# Power_Supply.net
KiCad netlist of a schematic drawn in Altium Designer
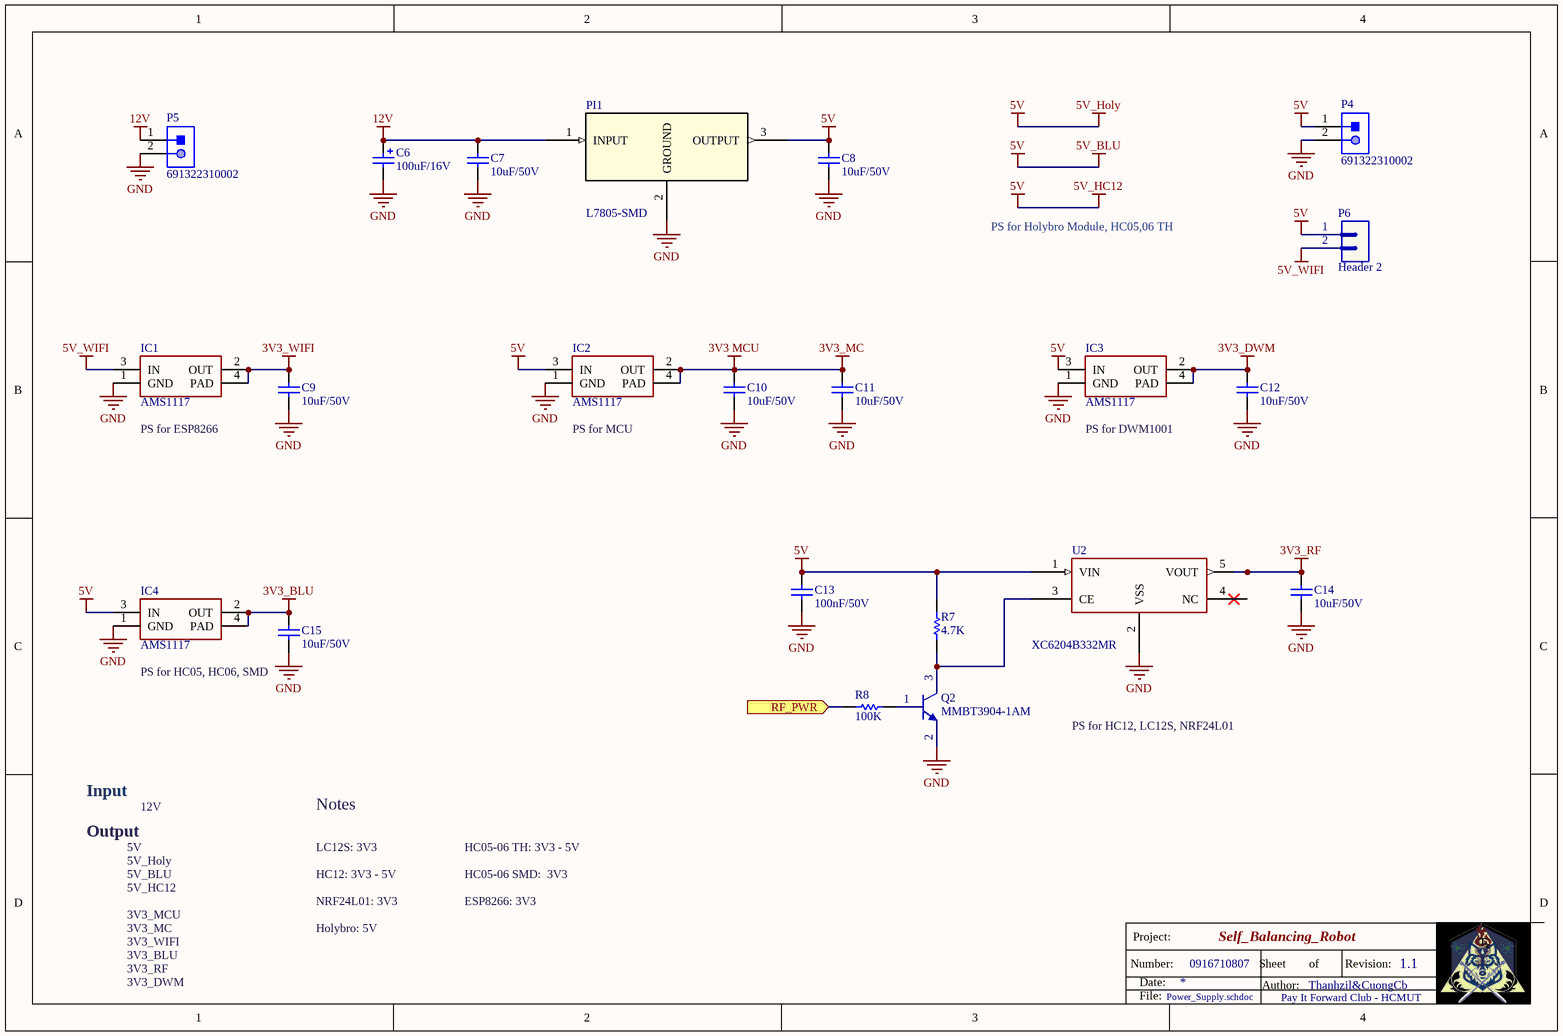
[diagram p0: Power_Supply.SchDoc]

(export (version "E")
  (design (tool "Eeschema 10.0.6"))
  (components
    (comp (ref "C6")
      (value "100uF/16V")
      (footprint "CAP-SM-AL-SIZE-D-D6L6")
      (description "CAP ALUM 100UF 20% 16V SMD")
      (fields
        (field (name "MANUFACTURER") "Nichicon")
        (field (name "MANUFACTURER PART NUMBER") "UWX1C101MCL1GB")
      )
      (libsource (lib "Capacitor") (part "Cap-Al-100uF-16V-D6L5"))
    )
    (comp (ref "C7")
      (value "10uF/50V")
      (footprint "CAP-SM-0805")
      (description "CAP CER 10UF 50V X5R 0805")
      (fields
        (field (name "MANUFACTURER") "Yageo")
        (field (name "MANUFACTURER PART NUMBER") "CC0805KKX5R9BB106")
      )
      (libsource (lib "Capacitor") (part "Cap-10uF-50V-0805"))
    )
    (comp (ref "C8")
      (value "10uF/50V")
      (footprint "CAP-SM-0805")
      (description "CAP CER 10UF 50V X5R 0805")
      (fields
        (field (name "MANUFACTURER") "Yageo")
        (field (name "MANUFACTURER PART NUMBER") "CC0805KKX5R9BB106")
      )
      (libsource (lib "Capacitor") (part "Cap-10uF-50V-0805"))
    )
    (comp (ref "C9")
      (value "10uF/50V")
      (footprint "CAP-SM-0805")
      (description "CAP CER 10UF 50V X5R 0805")
      (fields
        (field (name "MANUFACTURER") "Yageo")
        (field (name "MANUFACTURER PART NUMBER") "CC0805KKX5R9BB106")
      )
      (libsource (lib "Capacitor") (part "Cap-10uF-50V-0805"))
    )
    (comp (ref "C10")
      (value "10uF/50V")
      (footprint "CAP-SM-0805")
      (description "CAP CER 10UF 50V X5R 0805")
      (fields
        (field (name "MANUFACTURER") "Yageo")
        (field (name "MANUFACTURER PART NUMBER") "CC0805KKX5R9BB106")
      )
      (libsource (lib "Capacitor") (part "Cap-10uF-50V-0805"))
    )
    (comp (ref "C11")
      (value "10uF/50V")
      (footprint "CAP-SM-0805")
      (description "CAP CER 10UF 50V X5R 0805")
      (fields
        (field (name "MANUFACTURER") "Yageo")
        (field (name "MANUFACTURER PART NUMBER") "CC0805KKX5R9BB106")
      )
      (libsource (lib "Capacitor") (part "Cap-10uF-50V-0805"))
    )
    (comp (ref "C12")
      (value "10uF/50V")
      (footprint "CAP-SM-0805")
      (description "CAP CER 10UF 50V X5R 0805")
      (fields
        (field (name "MANUFACTURER") "Yageo")
        (field (name "MANUFACTURER PART NUMBER") "CC0805KKX5R9BB106")
      )
      (libsource (lib "Capacitor") (part "Cap-10uF-50V-0805"))
    )
    (comp (ref "C13")
      (value "100nF/50V")
      (footprint "CAP-SM-0805")
      (description "CAP CER 0.1UF 50V Y5V 0805")
      (fields
        (field (name "MANUFACTURER") "Samsung Electro-Mechanics")
        (field (name "MANUFACTURER PART NUMBER") "CL21F104ZBCNNNC")
      )
      (libsource (lib "Capacitor") (part "Cap-100nF-50V-0805"))
    )
    (comp (ref "C14")
      (value "10uF/50V")
      (footprint "CAP-SM-0805")
      (description "CAP CER 10UF 50V X5R 0805")
      (fields
        (field (name "MANUFACTURER") "Yageo")
        (field (name "MANUFACTURER PART NUMBER") "CC0805KKX5R9BB106")
      )
      (libsource (lib "Capacitor") (part "Cap-10uF-50V-0805"))
    )
    (comp (ref "C15")
      (value "10uF/50V")
      (footprint "CAP-SM-0805")
      (description "CAP CER 10UF 50V X5R 0805")
      (fields
        (field (name "MANUFACTURER") "Yageo")
        (field (name "MANUFACTURER PART NUMBER") "CC0805KKX5R9BB106")
      )
      (libsource (lib "Capacitor") (part "Cap-10uF-50V-0805"))
    )
    (comp (ref "IC1")
      (value "AMS1117")
      (footprint "SOT223")
      (description "Available in 1.8V, 2.5V, 2.85V, 3.3V, 5V, and  Adjustable Versions")
      (libsource (lib "PI") (part "AMS1117"))
    )
    (comp (ref "IC2")
      (value "AMS1117")
      (footprint "SOT223")
      (description "Available in 1.8V, 2.5V, 2.85V, 3.3V, 5V, and  Adjustable Versions")
      (libsource (lib "PI") (part "AMS1117"))
    )
    (comp (ref "IC3")
      (value "AMS1117")
      (footprint "SOT223")
      (description "Available in 1.8V, 2.5V, 2.85V, 3.3V, 5V, and  Adjustable Versions")
      (libsource (lib "PI") (part "AMS1117"))
    )
    (comp (ref "IC4")
      (value "AMS1117")
      (footprint "SOT223")
      (description "Available in 1.8V, 2.5V, 2.85V, 3.3V, 5V, and  Adjustable Versions")
      (libsource (lib "PI") (part "AMS1117"))
    )
    (comp (ref "P4")
      (value "691322310002")
      (footprint "Project_Xe_Can_Bang:691322310002")
      (description "WR-TBL Serie 322 Horizontal PCB Header, Pluggable, pitch 3.81mm, 2p")
      (fields (field (name "PUBLISHER") "Wurth Elektronik"))
      (libsource (lib "Project_Xe_Can_Bang") (part "691322310002"))
    )
    (comp (ref "P5")
      (value "691322310002")
      (footprint "Project_Xe_Can_Bang:691322310002")
      (description "WR-TBL Serie 322 Horizontal PCB Header, Pluggable, pitch 3.81mm, 2p")
      (fields (field (name "PUBLISHER") "Wurth Elektronik"))
      (libsource (lib "Project_Xe_Can_Bang") (part "691322310002"))
    )
    (comp (ref "P6")
      (value "Header 2")
      (footprint "Project_Xe_Can_Bang:JP2")
      (description "Header, 2-Pin")
      (fields (field (name "PUBLISHER") "Altium Limited"))
      (libsource (lib "Project_Xe_Can_Bang") (part "Header 2"))
    )
    (comp (ref "PI1")
      (value "L7805-SMD")
      (footprint "D2PAK_STM")
      (description "No Description Available")
      (fields
        (field (name "MANUFACTURER_PART_NUMBER") "L7805CD2T-TR")
        (field (name "COPYRIGHT") "Copyright (C) 2018 Accelerated Designs. All rights reserved")
      )
      (libsource (lib "Project_Xe_Can_Bang") (part "L7805CD2T-TR"))
    )
    (comp (ref "Q2")
      (value "MMBT3904-1AM")
      (footprint "SOT23_NEX")
      (libsource (lib "BJT") (part "MMBT3904-1AM"))
    )
    (comp (ref "R7")
      (value "4.7K")
      (footprint "Resistor:RES-SM-0805")
      (description "RES SMD 4.7K OHM 5% 1/8W 0805")
      (fields
        (field (name "MANUFACTURER") "Yageo")
        (field (name "MANUFACTURER PART NUMBER") "RC0805JR-074K7L")
      )
      (libsource (lib "Resistor") (part "Res-4.7K-0805"))
    )
    (comp (ref "R8")
      (value "100K")
      (footprint "Resistor:RES-SM-0805")
      (description "RES 0 OHM JUMPER 0805")
      (fields
        (field (name "MANUFACTURER") "Vishay Dale")
        (field (name "MANUFACTURER PART NUMBER") "WSL080500000ZEA9")
      )
      (libsource (lib "Resistor") (part "Res-100K-0805"))
    )
    (comp (ref "U2")
      (value "XC6204B332MR")
      (footprint "XC6204/05_SOT-00")
      (fields (field (name "COPYRIGHT") "Copyright (C) 2018 Accelerated Designs. All rights reserved"))
      (libsource (lib "PI") (part "XC6204B332MR"))
    )
  )
  (nets
    (net (code "18") (name "/RF_PWR") (class "Default")
      (node (ref "R8") (pin "1") (pinfunction "1_1") (pintype "passive"))
    )
    (net (code "19") (name "3V3 MCU") (class "Default")
      (node (ref "C10") (pin "2") (pinfunction "2_2") (pintype "passive"))
      (node (ref "C11") (pin "2") (pinfunction "2_2") (pintype "passive"))
      (node (ref "IC2") (pin "2") (pinfunction "OUT_2") (pintype "passive"))
      (node (ref "IC2") (pin "4") (pinfunction "PAD_4") (pintype "passive"))
    )
    (net (code "20") (name "3V3_BLU") (class "Default")
      (node (ref "C15") (pin "2") (pinfunction "2_2") (pintype "passive"))
      (node (ref "IC4") (pin "2") (pinfunction "OUT_2") (pintype "passive"))
      (node (ref "IC4") (pin "4") (pinfunction "PAD_4") (pintype "passive"))
    )
    (net (code "21") (name "3V3_DWM") (class "Default")
      (node (ref "C12") (pin "2") (pinfunction "2_2") (pintype "passive"))
      (node (ref "IC3") (pin "2") (pinfunction "OUT_2") (pintype "passive"))
      (node (ref "IC3") (pin "4") (pinfunction "PAD_4") (pintype "passive"))
    )
    (net (code "22") (name "3V3_RF") (class "Default")
      (node (ref "C14") (pin "2") (pinfunction "2_2") (pintype "passive"))
      (node (ref "U2") (pin "5") (pinfunction "VOUT_5") (pintype "output"))
    )
    (net (code "23") (name "3V3_WIFI") (class "Default")
      (node (ref "C9") (pin "2") (pinfunction "2_2") (pintype "passive"))
      (node (ref "IC1") (pin "2") (pinfunction "OUT_2") (pintype "passive"))
      (node (ref "IC1") (pin "4") (pinfunction "PAD_4") (pintype "passive"))
    )
    (net (code "24") (name "5V") (class "Default")
      (node (ref "C13") (pin "2") (pinfunction "2_2") (pintype "passive"))
      (node (ref "C8") (pin "2") (pinfunction "2_2") (pintype "passive"))
      (node (ref "IC2") (pin "3") (pinfunction "IN_3") (pintype "passive"))
      (node (ref "IC3") (pin "3") (pinfunction "IN_3") (pintype "passive"))
      (node (ref "IC4") (pin "3") (pinfunction "IN_3") (pintype "passive"))
      (node (ref "P4") (pin "1") (pinfunction "1_1") (pintype "passive"))
      (node (ref "P6") (pin "1") (pinfunction "1_1") (pintype "passive"))
      (node (ref "PI1") (pin "3") (pinfunction "OUTPUT_3") (pintype "output"))
      (node (ref "R7") (pin "2") (pinfunction "2_2") (pintype "passive"))
      (node (ref "U2") (pin "1") (pinfunction "VIN_1") (pintype "input"))
    )
    (net (code "25") (name "5V_WIFI") (class "Default")
      (node (ref "IC1") (pin "3") (pinfunction "IN_3") (pintype "passive"))
      (node (ref "P6") (pin "2") (pinfunction "2_2") (pintype "passive"))
    )
    (net (code "26") (name "12V") (class "Default")
      (node (ref "C6") (pin "1") (pinfunction "1_1") (pintype "passive"))
      (node (ref "C7") (pin "2") (pinfunction "2_2") (pintype "passive"))
      (node (ref "P5") (pin "1") (pinfunction "1_1") (pintype "passive"))
      (node (ref "PI1") (pin "1") (pinfunction "INPUT_1") (pintype "input"))
    )
    (net (code "27") (name "GND") (class "Default")
      (node (ref "C10") (pin "1") (pinfunction "1_1") (pintype "passive"))
      (node (ref "C11") (pin "1") (pinfunction "1_1") (pintype "passive"))
      (node (ref "C12") (pin "1") (pinfunction "1_1") (pintype "passive"))
      (node (ref "C13") (pin "1") (pinfunction "1_1") (pintype "passive"))
      (node (ref "C14") (pin "1") (pinfunction "1_1") (pintype "passive"))
      (node (ref "C15") (pin "1") (pinfunction "1_1") (pintype "passive"))
      (node (ref "C6") (pin "2") (pinfunction "2_2") (pintype "passive"))
      (node (ref "C7") (pin "1") (pinfunction "1_1") (pintype "passive"))
      (node (ref "C8") (pin "1") (pinfunction "1_1") (pintype "passive"))
      (node (ref "C9") (pin "1") (pinfunction "1_1") (pintype "passive"))
      (node (ref "IC1") (pin "1") (pinfunction "GND_1") (pintype "passive"))
      (node (ref "IC2") (pin "1") (pinfunction "GND_1") (pintype "passive"))
      (node (ref "IC3") (pin "1") (pinfunction "GND_1") (pintype "passive"))
      (node (ref "IC4") (pin "1") (pinfunction "GND_1") (pintype "passive"))
      (node (ref "P4") (pin "2") (pinfunction "2_2") (pintype "passive"))
      (node (ref "P5") (pin "2") (pinfunction "2_2") (pintype "passive"))
      (node (ref "PI1") (pin "2") (pinfunction "GROUND_2") (pintype "passive"))
      (node (ref "Q2") (pin "2") (pinfunction "E_2") (pintype "passive"))
      (node (ref "U2") (pin "2") (pinfunction "VSS_2") (pintype "passive"))
    )
    (net (code "28") (name "Net-(Q2-B)") (class "Default")
      (node (ref "Q2") (pin "1") (pinfunction "B_1") (pintype "passive"))
      (node (ref "R8") (pin "2") (pinfunction "2_2") (pintype "passive"))
    )
    (net (code "29") (name "Net-(Q2-C)") (class "Default")
      (node (ref "Q2") (pin "3") (pinfunction "C_3") (pintype "passive"))
      (node (ref "R7") (pin "1") (pinfunction "1_1") (pintype "passive"))
      (node (ref "U2") (pin "3") (pinfunction "CE_3") (pintype "passive"))
    )
    (net (code "30") (name "unconnected-(U2-NC-Pad4)") (class "Default")
      (node (ref "U2") (pin "4") (pinfunction "NC_4") (pintype "passive"))
    )
  )
)
